# cnc-power-panel.net
KiCad netlist of a schematic drawn in EAGLE
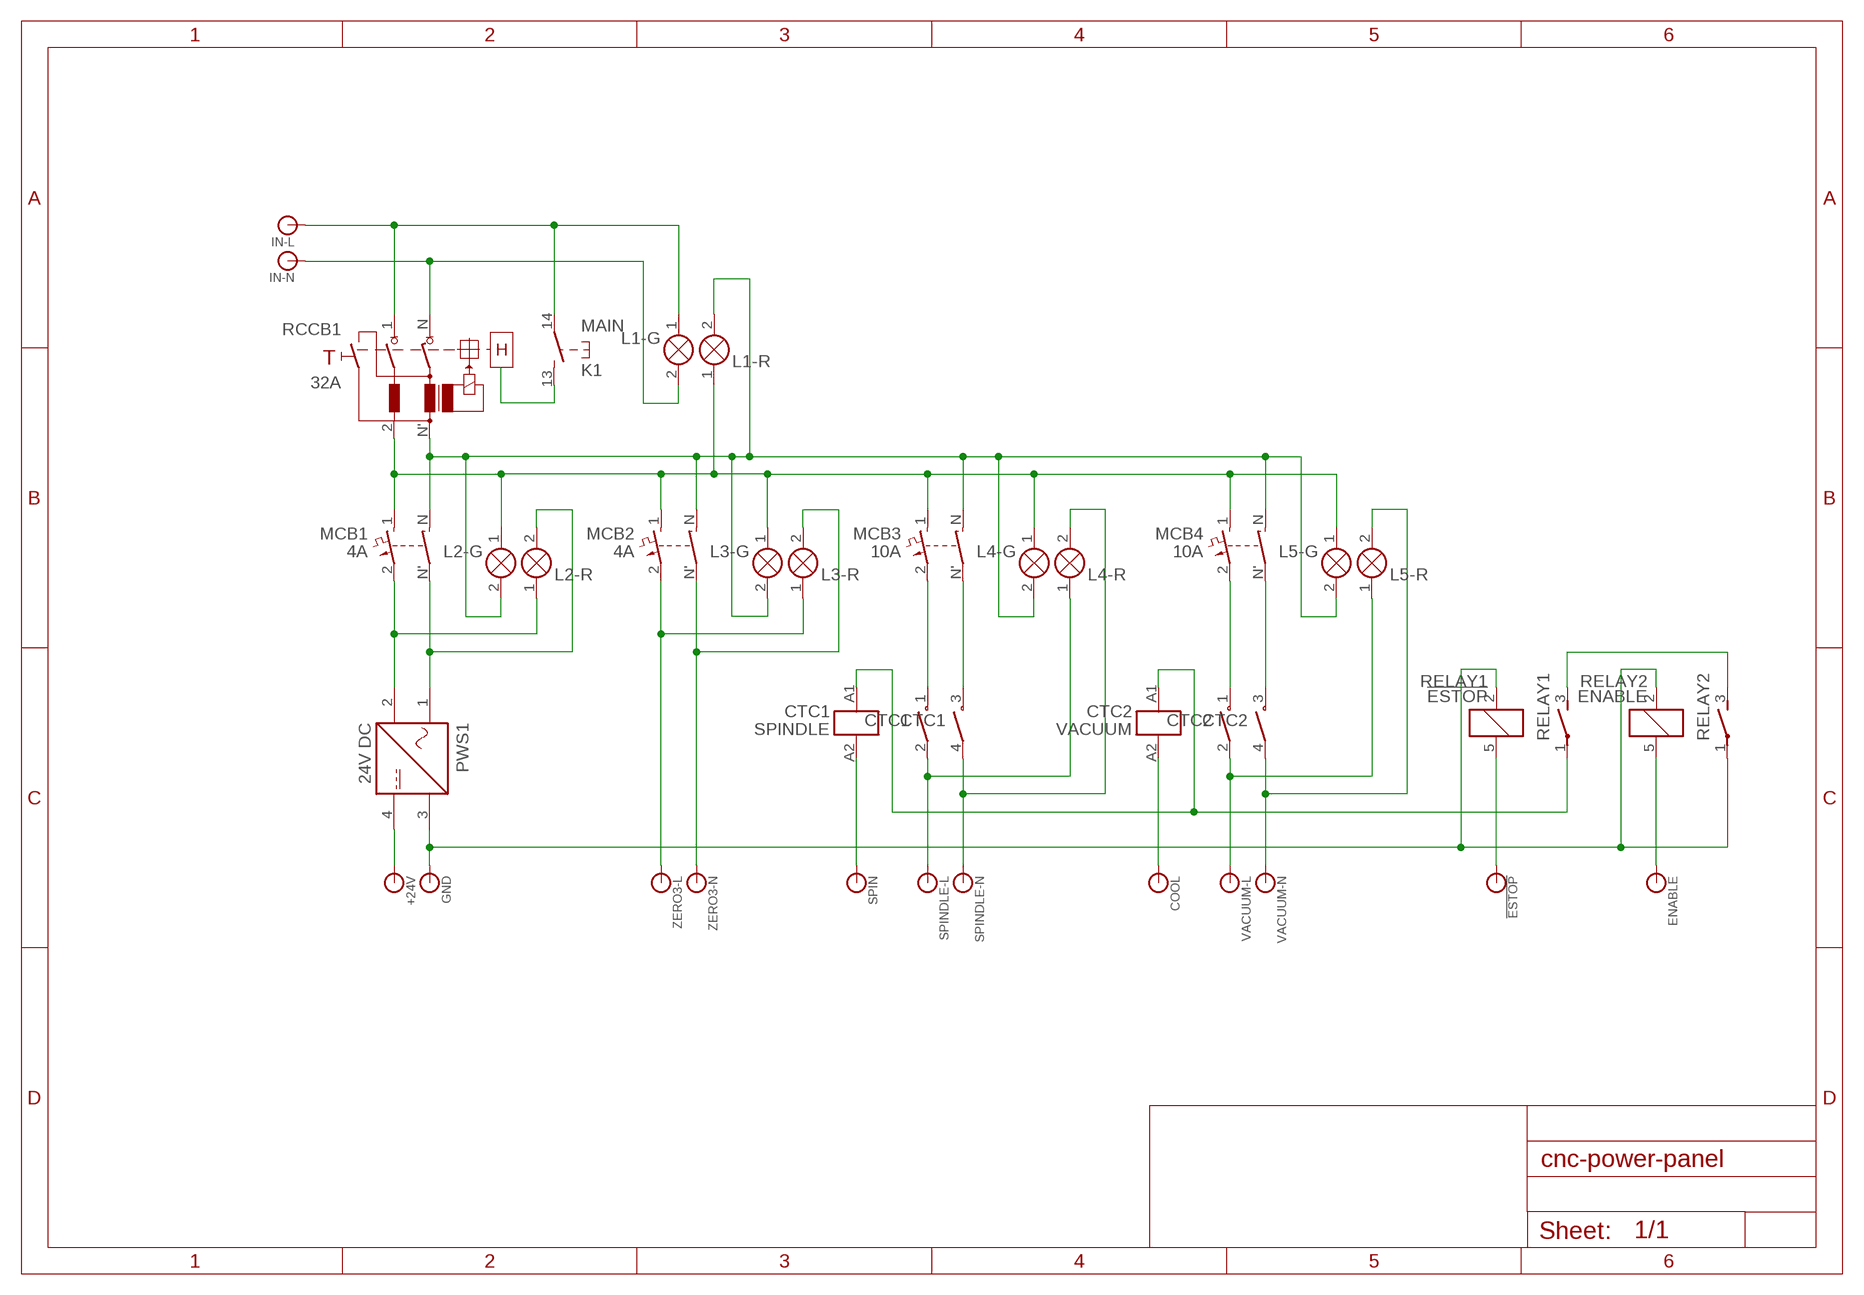
[diagram p0: schematic, sheet 1]

(export (version "E")
  (design (tool "Eeschema 10.0.6"))
  (components
    (comp (ref "!ESTOP")
      (value "BANANA_CONN")
      (footprint "eagle-import:BANANA_CONN")
      (libsource (lib "eagle-import") (part "BANANA_CONN"))
    )
    (comp (ref "+24V")
      (value "BANANA_CONN")
      (footprint "eagle-import:BANANA_CONN")
      (libsource (lib "eagle-import") (part "BANANA_CONN"))
    )
    (comp (ref "COOL")
      (value "BANANA_CONN")
      (footprint "eagle-import:BANANA_CONN")
      (libsource (lib "eagle-import") (part "BANANA_CONN"))
    )
    (comp (ref "CTC1")
      (value "SPINDLE")
      (footprint "eagle-import:HAUPTSCHUETZ_2-POL")
      (libsource (lib "eagle-import") (part "HAUPTSCHUETZ_2-POL"))
    )
    (comp (ref "CTC2")
      (value "VACUUM")
      (footprint "eagle-import:HAUPTSCHUETZ_2-POL")
      (libsource (lib "eagle-import") (part "HAUPTSCHUETZ_2-POL"))
    )
    (comp (ref "ENABLE")
      (value "BANANA_CONN")
      (footprint "eagle-import:BANANA_CONN")
      (libsource (lib "eagle-import") (part "BANANA_CONN"))
    )
    (comp (ref "GND")
      (value "BANANA_CONN")
      (footprint "eagle-import:BANANA_CONN")
      (libsource (lib "eagle-import") (part "BANANA_CONN"))
    )
    (comp (ref "IN-L")
      (value "BANANA_CONN")
      (footprint "eagle-import:BANANA_CONN")
      (libsource (lib "eagle-import") (part "BANANA_CONN"))
    )
    (comp (ref "IN-N")
      (value "BANANA_CONN")
      (footprint "eagle-import:BANANA_CONN")
      (libsource (lib "eagle-import") (part "BANANA_CONN"))
    )
    (comp (ref "K1")
      (value "MAIN")
      (footprint "eagle-import:EINTASTER")
      (libsource (lib "eagle-import") (part "TASTER_SCHLIESSER"))
    )
    (comp (ref "L1-G")
      (value "SIGNALLAMPE")
      (footprint "eagle-import:LAMPE")
      (libsource (lib "eagle-import") (part "SIGNALLAMPE"))
    )
    (comp (ref "L1-R")
      (value "SIGNALLAMPE")
      (footprint "eagle-import:LAMPE")
      (libsource (lib "eagle-import") (part "SIGNALLAMPE"))
    )
    (comp (ref "L2-G")
      (value "SIGNALLAMPE")
      (footprint "eagle-import:LAMPE")
      (libsource (lib "eagle-import") (part "SIGNALLAMPE"))
    )
    (comp (ref "L2-R")
      (value "SIGNALLAMPE")
      (footprint "eagle-import:LAMPE")
      (libsource (lib "eagle-import") (part "SIGNALLAMPE"))
    )
    (comp (ref "L3-G")
      (value "SIGNALLAMPE")
      (footprint "eagle-import:LAMPE")
      (libsource (lib "eagle-import") (part "SIGNALLAMPE"))
    )
    (comp (ref "L3-R")
      (value "SIGNALLAMPE")
      (footprint "eagle-import:LAMPE")
      (libsource (lib "eagle-import") (part "SIGNALLAMPE"))
    )
    (comp (ref "L4-G")
      (value "SIGNALLAMPE")
      (footprint "eagle-import:LAMPE")
      (libsource (lib "eagle-import") (part "SIGNALLAMPE"))
    )
    (comp (ref "L4-R")
      (value "SIGNALLAMPE")
      (footprint "eagle-import:LAMPE")
      (libsource (lib "eagle-import") (part "SIGNALLAMPE"))
    )
    (comp (ref "L5-G")
      (value "SIGNALLAMPE")
      (footprint "eagle-import:LAMPE")
      (libsource (lib "eagle-import") (part "SIGNALLAMPE"))
    )
    (comp (ref "L5-R")
      (value "SIGNALLAMPE")
      (footprint "eagle-import:LAMPE")
      (libsource (lib "eagle-import") (part "SIGNALLAMPE"))
    )
    (comp (ref "MCB1")
      (value "4A")
      (footprint "eagle-import:LEITUNGSSCHUTZSCHALTER_2-POL")
      (libsource (lib "eagle-import") (part "LEITUNGSSCHUTZSCHALTER_2-POL"))
    )
    (comp (ref "MCB2")
      (value "4A")
      (footprint "eagle-import:LEITUNGSSCHUTZSCHALTER_2-POL")
      (libsource (lib "eagle-import") (part "LEITUNGSSCHUTZSCHALTER_2-POL"))
    )
    (comp (ref "MCB3")
      (value "10A")
      (footprint "eagle-import:LEITUNGSSCHUTZSCHALTER_2-POL")
      (libsource (lib "eagle-import") (part "LEITUNGSSCHUTZSCHALTER_2-POL"))
    )
    (comp (ref "MCB4")
      (value "10A")
      (footprint "eagle-import:LEITUNGSSCHUTZSCHALTER_2-POL")
      (libsource (lib "eagle-import") (part "LEITUNGSSCHUTZSCHALTER_2-POL"))
    )
    (comp (ref "PWS1")
      (value "24V DC")
      (footprint "eagle-import:NETZTEIL_GLEICHSPANNUNG")
      (libsource (lib "eagle-import") (part "NETZTEIL_GLEICHSPANNUNG"))
    )
    (comp (ref "RCCB1")
      (value "32A")
      (footprint "eagle-import:FEHLER-STROM-SCHUTZSCHALTER_2-POL")
      (libsource (lib "eagle-import") (part "FEHLER-STROM-SCHUTZSCHALTER_2-POL"))
    )
    (comp (ref "RELAY1")
      (value "!ESTOP")
      (footprint "eagle-import:AZ8")
      (libsource (lib "eagle-import") (part "AZ8-FORM-A"))
    )
    (comp (ref "RELAY2")
      (value "ENABLE")
      (footprint "eagle-import:AZ8")
      (libsource (lib "eagle-import") (part "AZ8-FORM-A"))
    )
    (comp (ref "SPIN")
      (value "BANANA_CONN")
      (footprint "eagle-import:BANANA_CONN")
      (libsource (lib "eagle-import") (part "BANANA_CONN"))
    )
    (comp (ref "SPINDLE-L")
      (value "BANANA_CONN")
      (footprint "eagle-import:BANANA_CONN")
      (libsource (lib "eagle-import") (part "BANANA_CONN"))
    )
    (comp (ref "SPINDLE-N")
      (value "BANANA_CONN")
      (footprint "eagle-import:BANANA_CONN")
      (libsource (lib "eagle-import") (part "BANANA_CONN"))
    )
    (comp (ref "VACUUM-L")
      (value "BANANA_CONN")
      (footprint "eagle-import:BANANA_CONN")
      (libsource (lib "eagle-import") (part "BANANA_CONN"))
    )
    (comp (ref "VACUUM-N")
      (value "BANANA_CONN")
      (footprint "eagle-import:BANANA_CONN")
      (libsource (lib "eagle-import") (part "BANANA_CONN"))
    )
    (comp (ref "ZERO3-L")
      (value "BANANA_CONN")
      (footprint "eagle-import:BANANA_CONN")
      (libsource (lib "eagle-import") (part "BANANA_CONN"))
    )
    (comp (ref "ZERO3-N")
      (value "BANANA_CONN")
      (footprint "eagle-import:BANANA_CONN")
      (libsource (lib "eagle-import") (part "BANANA_CONN"))
    )
  )
  (nets
    (net (code "1") (name "Net-(!ESTOP-1)") (class "Default")
      (node (ref "!ESTOP") (pin "P$1") (pinfunction "1_P$1") (pintype "passive"))
      (node (ref "RELAY1") (pin "5") (pinfunction "2_5") (pintype "passive"))
    )
    (net (code "2") (name "Net-(+24V-1)") (class "Default")
      (node (ref "+24V") (pin "P$1") (pinfunction "1_P$1") (pintype "passive"))
      (node (ref "PWS1") (pin "4") (pinfunction "4_4") (pintype "passive"))
    )
    (net (code "3") (name "Net-(COOL-1)") (class "Default")
      (node (ref "COOL") (pin "P$1") (pinfunction "1_P$1") (pintype "passive"))
      (node (ref "CTC2") (pin "A2") (pinfunction "A2_A2") (pintype "input"))
    )
    (net (code "4") (name "Net-(CTC1-Pad3)") (class "Default")
      (node (ref "CTC1") (pin "3") (pinfunction "3_3") (pintype "passive"))
      (node (ref "MCB3") (pin "N'") (pinfunction "N_N'") (pintype "passive"))
    )
    (net (code "5") (name "Net-(CTC1B-3)") (class "Default")
      (node (ref "CTC1") (pin "1") (pinfunction "3_1") (pintype "passive"))
      (node (ref "MCB3") (pin "2") (pinfunction "2_2") (pintype "passive"))
    )
    (net (code "6") (name "Net-(CTC1B-4)") (class "Default")
      (node (ref "CTC1") (pin "2") (pinfunction "4_2") (pintype "passive"))
      (node (ref "L4-R") (pin "1") (pinfunction "X1_1") (pintype "passive"))
      (node (ref "SPINDLE-L") (pin "P$1") (pinfunction "1_P$1") (pintype "passive"))
    )
    (net (code "7") (name "Net-(CTC2-Pad3)") (class "Default")
      (node (ref "CTC2") (pin "3") (pinfunction "3_3") (pintype "passive"))
      (node (ref "MCB4") (pin "N'") (pinfunction "N_N'") (pintype "passive"))
    )
    (net (code "8") (name "Net-(CTC2B-3)") (class "Default")
      (node (ref "CTC2") (pin "1") (pinfunction "3_1") (pintype "passive"))
      (node (ref "MCB4") (pin "2") (pinfunction "2_2") (pintype "passive"))
    )
    (net (code "9") (name "Net-(CTC2B-4)") (class "Default")
      (node (ref "CTC2") (pin "2") (pinfunction "4_2") (pintype "passive"))
      (node (ref "L5-R") (pin "1") (pinfunction "X1_1") (pintype "passive"))
      (node (ref "VACUUM-L") (pin "P$1") (pinfunction "1_P$1") (pintype "passive"))
    )
    (net (code "10") (name "Net-(ENABLE-1)") (class "Default")
      (node (ref "ENABLE") (pin "P$1") (pinfunction "1_P$1") (pintype "passive"))
      (node (ref "RELAY2") (pin "5") (pinfunction "2_5") (pintype "passive"))
    )
    (net (code "11") (name "Net-(GND-1)") (class "Default")
      (node (ref "GND") (pin "P$1") (pinfunction "1_P$1") (pintype "passive"))
      (node (ref "PWS1") (pin "3") (pinfunction "3_3") (pintype "passive"))
      (node (ref "RELAY1") (pin "2") (pinfunction "1_2") (pintype "passive"))
      (node (ref "RELAY2") (pin "1") (pinfunction "P_1") (pintype "passive"))
      (node (ref "RELAY2") (pin "2") (pinfunction "1_2") (pintype "passive"))
    )
    (net (code "12") (name "Net-(IN-L-1)") (class "Default")
      (node (ref "IN-L") (pin "P$1") (pinfunction "1_P$1") (pintype "passive"))
      (node (ref "K1") (pin "14") (pinfunction "14_14") (pintype "passive"))
      (node (ref "L1-G") (pin "1") (pinfunction "X1_1") (pintype "passive"))
      (node (ref "RCCB1") (pin "1") (pinfunction "1_1") (pintype "passive"))
    )
    (net (code "13") (name "Net-(IN-N-1)") (class "Default")
      (node (ref "IN-N") (pin "P$1") (pinfunction "1_P$1") (pintype "passive"))
      (node (ref "L1-G") (pin "2") (pinfunction "X2_2") (pintype "passive"))
      (node (ref "RCCB1") (pin "N") (pinfunction "N_N") (pintype "passive"))
    )
    (net (code "14") (name "Net-(L1-R-X1)") (class "Default")
      (node (ref "L1-R") (pin "1") (pinfunction "X1_1") (pintype "passive"))
      (node (ref "L2-G") (pin "1") (pinfunction "X1_1") (pintype "passive"))
      (node (ref "L3-G") (pin "1") (pinfunction "X1_1") (pintype "passive"))
      (node (ref "L4-G") (pin "1") (pinfunction "X1_1") (pintype "passive"))
      (node (ref "L5-G") (pin "1") (pinfunction "X1_1") (pintype "passive"))
      (node (ref "MCB1") (pin "1") (pinfunction "1_1") (pintype "passive"))
      (node (ref "MCB2") (pin "1") (pinfunction "1_1") (pintype "passive"))
      (node (ref "MCB3") (pin "1") (pinfunction "1_1") (pintype "passive"))
      (node (ref "MCB4") (pin "1") (pinfunction "1_1") (pintype "passive"))
      (node (ref "RCCB1") (pin "2") (pinfunction "2_2") (pintype "passive"))
    )
    (net (code "15") (name "Net-(L1-R-X2)") (class "Default")
      (node (ref "L1-R") (pin "2") (pinfunction "X2_2") (pintype "passive"))
      (node (ref "L2-G") (pin "2") (pinfunction "X2_2") (pintype "passive"))
      (node (ref "L3-G") (pin "2") (pinfunction "X2_2") (pintype "passive"))
      (node (ref "L4-G") (pin "2") (pinfunction "X2_2") (pintype "passive"))
      (node (ref "L5-G") (pin "2") (pinfunction "X2_2") (pintype "passive"))
      (node (ref "MCB1") (pin "N") (pinfunction "N_N") (pintype "passive"))
      (node (ref "MCB2") (pin "N") (pinfunction "N_N") (pintype "passive"))
      (node (ref "MCB3") (pin "N") (pinfunction "N_N") (pintype "passive"))
      (node (ref "MCB4") (pin "N") (pinfunction "N_N") (pintype "passive"))
      (node (ref "RCCB1") (pin "N'") (pinfunction "N'_N'") (pintype "passive"))
    )
    (net (code "16") (name "Net-(L2-R-X1)") (class "Default")
      (node (ref "L2-R") (pin "1") (pinfunction "X1_1") (pintype "passive"))
      (node (ref "MCB1") (pin "2") (pinfunction "2_2") (pintype "passive"))
      (node (ref "PWS1") (pin "2") (pinfunction "2_2") (pintype "passive"))
    )
    (net (code "17") (name "Net-(L2-R-X2)") (class "Default")
      (node (ref "L2-R") (pin "2") (pinfunction "X2_2") (pintype "passive"))
      (node (ref "MCB1") (pin "N'") (pinfunction "N_N'") (pintype "passive"))
      (node (ref "PWS1") (pin "1") (pinfunction "1_1") (pintype "passive"))
    )
    (net (code "18") (name "Net-(L3-R-X1)") (class "Default")
      (node (ref "L3-R") (pin "1") (pinfunction "X1_1") (pintype "passive"))
      (node (ref "MCB2") (pin "2") (pinfunction "2_2") (pintype "passive"))
      (node (ref "ZERO3-L") (pin "P$1") (pinfunction "1_P$1") (pintype "passive"))
    )
    (net (code "19") (name "Net-(L3-R-X2)") (class "Default")
      (node (ref "L3-R") (pin "2") (pinfunction "X2_2") (pintype "passive"))
      (node (ref "MCB2") (pin "N'") (pinfunction "N_N'") (pintype "passive"))
      (node (ref "ZERO3-N") (pin "P$1") (pinfunction "1_P$1") (pintype "passive"))
    )
    (net (code "20") (name "Net-(L4-R-X2)") (class "Default")
      (node (ref "CTC1") (pin "4") (pinfunction "4_4") (pintype "passive"))
      (node (ref "L4-R") (pin "2") (pinfunction "X2_2") (pintype "passive"))
      (node (ref "SPINDLE-N") (pin "P$1") (pinfunction "1_P$1") (pintype "passive"))
    )
    (net (code "21") (name "Net-(L5-R-X2)") (class "Default")
      (node (ref "CTC2") (pin "4") (pinfunction "4_4") (pintype "passive"))
      (node (ref "L5-R") (pin "2") (pinfunction "X2_2") (pintype "passive"))
      (node (ref "VACUUM-N") (pin "P$1") (pinfunction "1_P$1") (pintype "passive"))
    )
    (net (code "22") (name "Net-(RELAY1A-P)") (class "Default")
      (node (ref "CTC1") (pin "A1") (pinfunction "A1_A1") (pintype "input"))
      (node (ref "CTC2") (pin "A1") (pinfunction "A1_A1") (pintype "input"))
      (node (ref "RELAY1") (pin "1") (pinfunction "P_1") (pintype "passive"))
    )
    (net (code "23") (name "Net-(RELAY1A-S)") (class "Default")
      (node (ref "RELAY1") (pin "3") (pinfunction "S_3") (pintype "passive"))
      (node (ref "RELAY2") (pin "3") (pinfunction "S_3") (pintype "passive"))
    )
    (net (code "24") (name "Net-(SPIN-1)") (class "Default")
      (node (ref "CTC1") (pin "A2") (pinfunction "A2_A2") (pintype "input"))
      (node (ref "SPIN") (pin "P$1") (pinfunction "1_P$1") (pintype "passive"))
    )
    (net (code "25") (name "unconnected-(K1-Pad13)") (class "Default")
      (node (ref "K1") (pin "13") (pinfunction "13_13") (pintype "passive"))
    )
  )
)
